# LDOs.net
KiCad netlist of a schematic drawn in Altium Designer
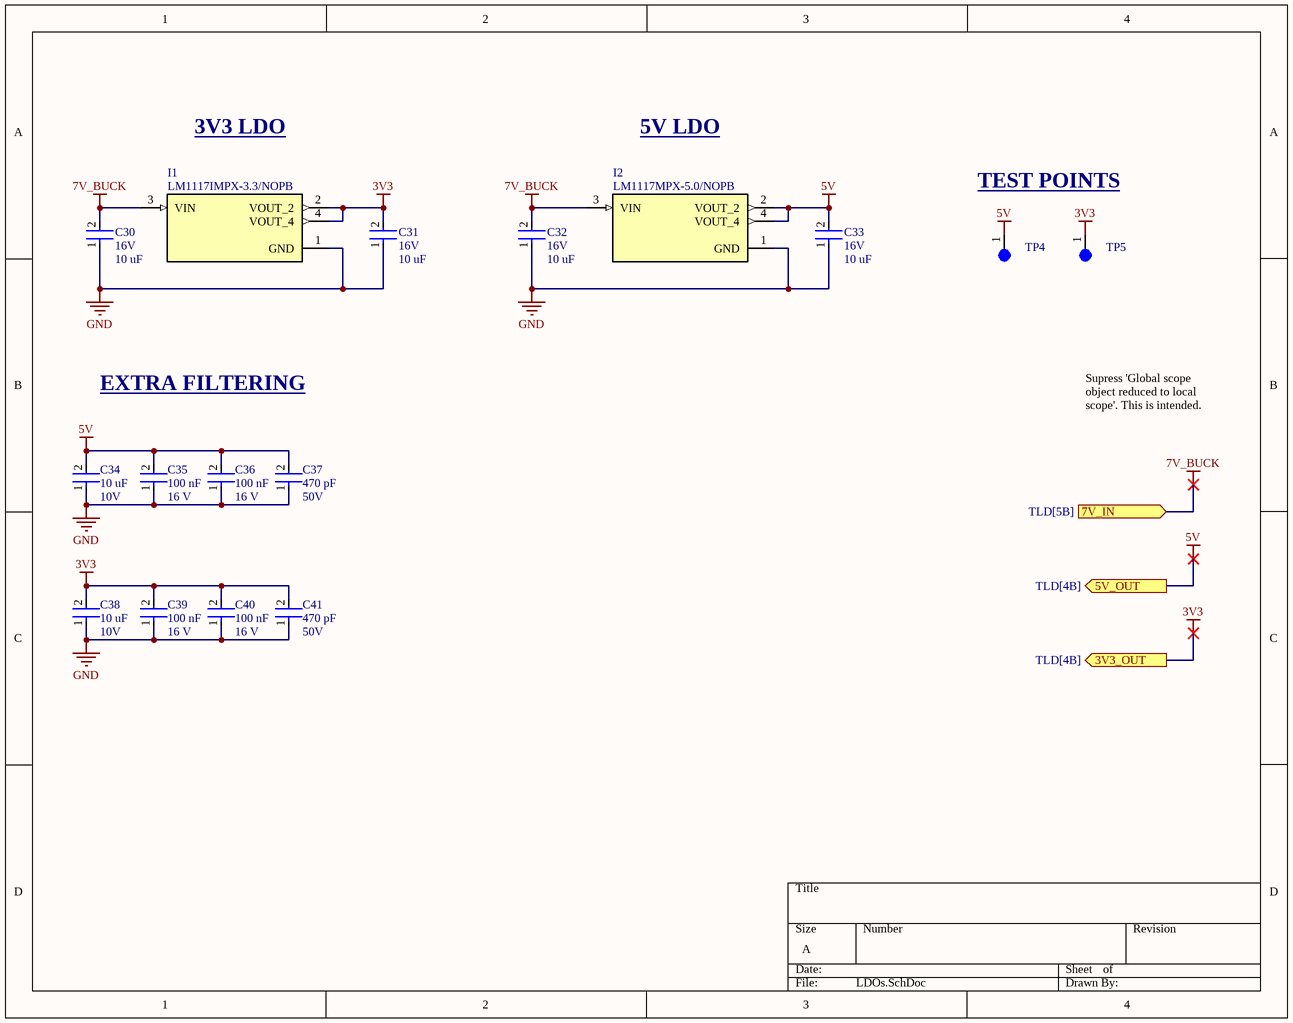
[diagram p0: LDOs.SchDoc]

(export (version "E")
  (design (tool "Eeschema 10.0.6"))
  (components
    (comp (ref "C30")
      (value "293D106X9016A2TE3")
      (footprint "CAP-1206")
      (description "CAP TANT 10UF 10% 16V 1206")
      (fields (field (name "VOLTAGE") "16V") (field (name "CAPACITANCE") "10 uF"))
      (libsource (lib "JLC_25") (part "CAP-10U-0004"))
    )
    (comp (ref "C31")
      (value "293D106X9016A2TE3")
      (footprint "CAP-1206")
      (description "CAP TANT 10UF 10% 16V 1206")
      (fields (field (name "VOLTAGE") "16V") (field (name "CAPACITANCE") "10 uF"))
      (libsource (lib "JLC_25") (part "CAP-10U-0004"))
    )
    (comp (ref "C32")
      (value "293D106X9016A2TE3")
      (footprint "CAP-1206")
      (description "CAP TANT 10UF 10% 16V 1206")
      (fields (field (name "VOLTAGE") "16V") (field (name "CAPACITANCE") "10 uF"))
      (libsource (lib "JLC_25") (part "CAP-10U-0004"))
    )
    (comp (ref "C33")
      (value "293D106X9016A2TE3")
      (footprint "CAP-1206")
      (description "CAP TANT 10UF 10% 16V 1206")
      (fields (field (name "VOLTAGE") "16V") (field (name "CAPACITANCE") "10 uF"))
      (libsource (lib "JLC_25") (part "CAP-10U-0004"))
    )
    (comp (ref "C34")
      (value "CC0603KRX5R6BB106")
      (footprint "CAP-0603")
      (description "CAP CER 10UF 10V X5R 0603")
      (fields (field (name "VOLTAGE") "10V") (field (name "CAPACITANCE") "10 uF"))
      (libsource (lib "JLC_25") (part "CAP-10U-0001"))
    )
    (comp (ref "C35")
      (value "CC0402KRX7R7BB104")
      (footprint "CAP-0402")
      (description "CAP CER 0.1UF 16V X7R 0402")
      (fields (field (name "VOLTAGE RATING") "16 V") (field (name "CAPACITANCE") "100 nF"))
      (libsource (lib "JLC_25") (part "CAP-0.1U-0001"))
    )
    (comp (ref "C36")
      (value "CC0402KRX7R7BB104")
      (footprint "CAP-0402")
      (description "CAP CER 0.1UF 16V X7R 0402")
      (fields (field (name "VOLTAGE RATING") "16 V") (field (name "CAPACITANCE") "100 nF"))
      (libsource (lib "JLC_25") (part "CAP-0.1U-0001"))
    )
    (comp (ref "C37")
      (value "CC0805JRNPO9BN471")
      (footprint "CAP-0805")
      (description "CAP CER 470PF 50V C0G/NPO 0805")
      (fields (field (name "VOLTAGE") "50V") (field (name "CAPACITANCE") "470 pF"))
      (libsource (lib "JLC_25") (part "CAP-470P-0001"))
    )
    (comp (ref "C38")
      (value "CC0603KRX5R6BB106")
      (footprint "CAP-0603")
      (description "CAP CER 10UF 10V X5R 0603")
      (fields (field (name "VOLTAGE") "10V") (field (name "CAPACITANCE") "10 uF"))
      (libsource (lib "JLC_25") (part "CAP-10U-0001"))
    )
    (comp (ref "C39")
      (value "CC0402KRX7R7BB104")
      (footprint "CAP-0402")
      (description "CAP CER 0.1UF 16V X7R 0402")
      (fields (field (name "VOLTAGE RATING") "16 V") (field (name "CAPACITANCE") "100 nF"))
      (libsource (lib "JLC_25") (part "CAP-0.1U-0001"))
    )
    (comp (ref "C40")
      (value "CC0402KRX7R7BB104")
      (footprint "CAP-0402")
      (description "CAP CER 0.1UF 16V X7R 0402")
      (fields (field (name "VOLTAGE RATING") "16 V") (field (name "CAPACITANCE") "100 nF"))
      (libsource (lib "JLC_25") (part "CAP-0.1U-0001"))
    )
    (comp (ref "C41")
      (value "CC0805JRNPO9BN471")
      (footprint "CAP-0805")
      (description "CAP CER 470PF 50V C0G/NPO 0805")
      (fields (field (name "VOLTAGE") "50V") (field (name "CAPACITANCE") "470 pF"))
      (libsource (lib "JLC_25") (part "CAP-470P-0001"))
    )
    (comp (ref "I1")
      (value "LM1117IMPX-3.3/NOPB")
      (footprint "IC-SOT-223-4")
      (description "IC REG LIN 3.3V 800MA SOT223-4")
      (libsource (lib "JLC_25") (part "IC_LDO_3V3_0001"))
    )
    (comp (ref "I2")
      (value "LM1117MPX-5.0/NOPB")
      (footprint "IC-SOT-223-4")
      (description "IC REG LINEAR 5V 800MA SOT223-4")
      (libsource (lib "JLC_25") (part "IC_LDO_5V_0001"))
    )
    (comp (ref "TP4")
      (value "5003")
      (footprint "TEST-POINT-0001")
      (description "Oranange PC Test Point, Miniature Phoisphor Bronze Silver Plating Through Hole Mounting Type")
      (libsource (lib "*") (part "TEST-POINT-0001"))
    )
    (comp (ref "TP5")
      (value "5003")
      (footprint "TEST-POINT-0001")
      (description "Oranange PC Test Point, Miniature Phoisphor Bronze Silver Plating Through Hole Mounting Type")
      (libsource (lib "*") (part "TEST-POINT-0001"))
    )
  )
  (nets
    (net (code "1") (name "3V3") (class "Default")
      (node (ref "C31") (pin "2") (pinfunction "2_2") (pintype "passive"))
      (node (ref "C38") (pin "2") (pinfunction "2_2") (pintype "passive"))
      (node (ref "C39") (pin "2") (pinfunction "2_2") (pintype "passive"))
      (node (ref "C40") (pin "2") (pinfunction "2_2") (pintype "passive"))
      (node (ref "C41") (pin "2") (pinfunction "2_2") (pintype "passive"))
      (node (ref "I1") (pin "2") (pinfunction "VOUT_2_2") (pintype "output"))
      (node (ref "I1") (pin "4") (pinfunction "VOUT_4_4") (pintype "output"))
      (node (ref "TP5") (pin "1") (pinfunction "0_1") (pintype "passive"))
    )
    (net (code "2") (name "5V") (class "Default")
      (node (ref "C33") (pin "2") (pinfunction "2_2") (pintype "passive"))
      (node (ref "C34") (pin "2") (pinfunction "2_2") (pintype "passive"))
      (node (ref "C35") (pin "2") (pinfunction "2_2") (pintype "passive"))
      (node (ref "C36") (pin "2") (pinfunction "2_2") (pintype "passive"))
      (node (ref "C37") (pin "2") (pinfunction "2_2") (pintype "passive"))
      (node (ref "I2") (pin "2") (pinfunction "VOUT_2_2") (pintype "output"))
      (node (ref "I2") (pin "4") (pinfunction "VOUT_4_4") (pintype "output"))
      (node (ref "TP4") (pin "1") (pinfunction "0_1") (pintype "passive"))
    )
    (net (code "3") (name "7V_BUCK") (class "Default")
      (node (ref "C30") (pin "2") (pinfunction "2_2") (pintype "passive"))
      (node (ref "C32") (pin "2") (pinfunction "2_2") (pintype "passive"))
      (node (ref "I1") (pin "3") (pinfunction "VIN_3") (pintype "input"))
      (node (ref "I2") (pin "3") (pinfunction "VIN_3") (pintype "input"))
    )
    (net (code "4") (name "GND") (class "Default")
      (node (ref "C30") (pin "1") (pinfunction "1_1") (pintype "passive"))
      (node (ref "C31") (pin "1") (pinfunction "1_1") (pintype "passive"))
      (node (ref "C32") (pin "1") (pinfunction "1_1") (pintype "passive"))
      (node (ref "C33") (pin "1") (pinfunction "1_1") (pintype "passive"))
      (node (ref "C34") (pin "1") (pinfunction "1_1") (pintype "passive"))
      (node (ref "C35") (pin "1") (pinfunction "1_1") (pintype "passive"))
      (node (ref "C36") (pin "1") (pinfunction "1_1") (pintype "passive"))
      (node (ref "C37") (pin "1") (pinfunction "1_1") (pintype "passive"))
      (node (ref "C38") (pin "1") (pinfunction "1_1") (pintype "passive"))
      (node (ref "C39") (pin "1") (pinfunction "1_1") (pintype "passive"))
      (node (ref "C40") (pin "1") (pinfunction "1_1") (pintype "passive"))
      (node (ref "C41") (pin "1") (pinfunction "1_1") (pintype "passive"))
      (node (ref "I1") (pin "1") (pinfunction "GND_1") (pintype "power_in"))
      (node (ref "I2") (pin "1") (pinfunction "GND_1") (pintype "power_in"))
    )
  )
)
